# Heater_ADC.net
KiCad netlist of a schematic drawn in Altium Designer
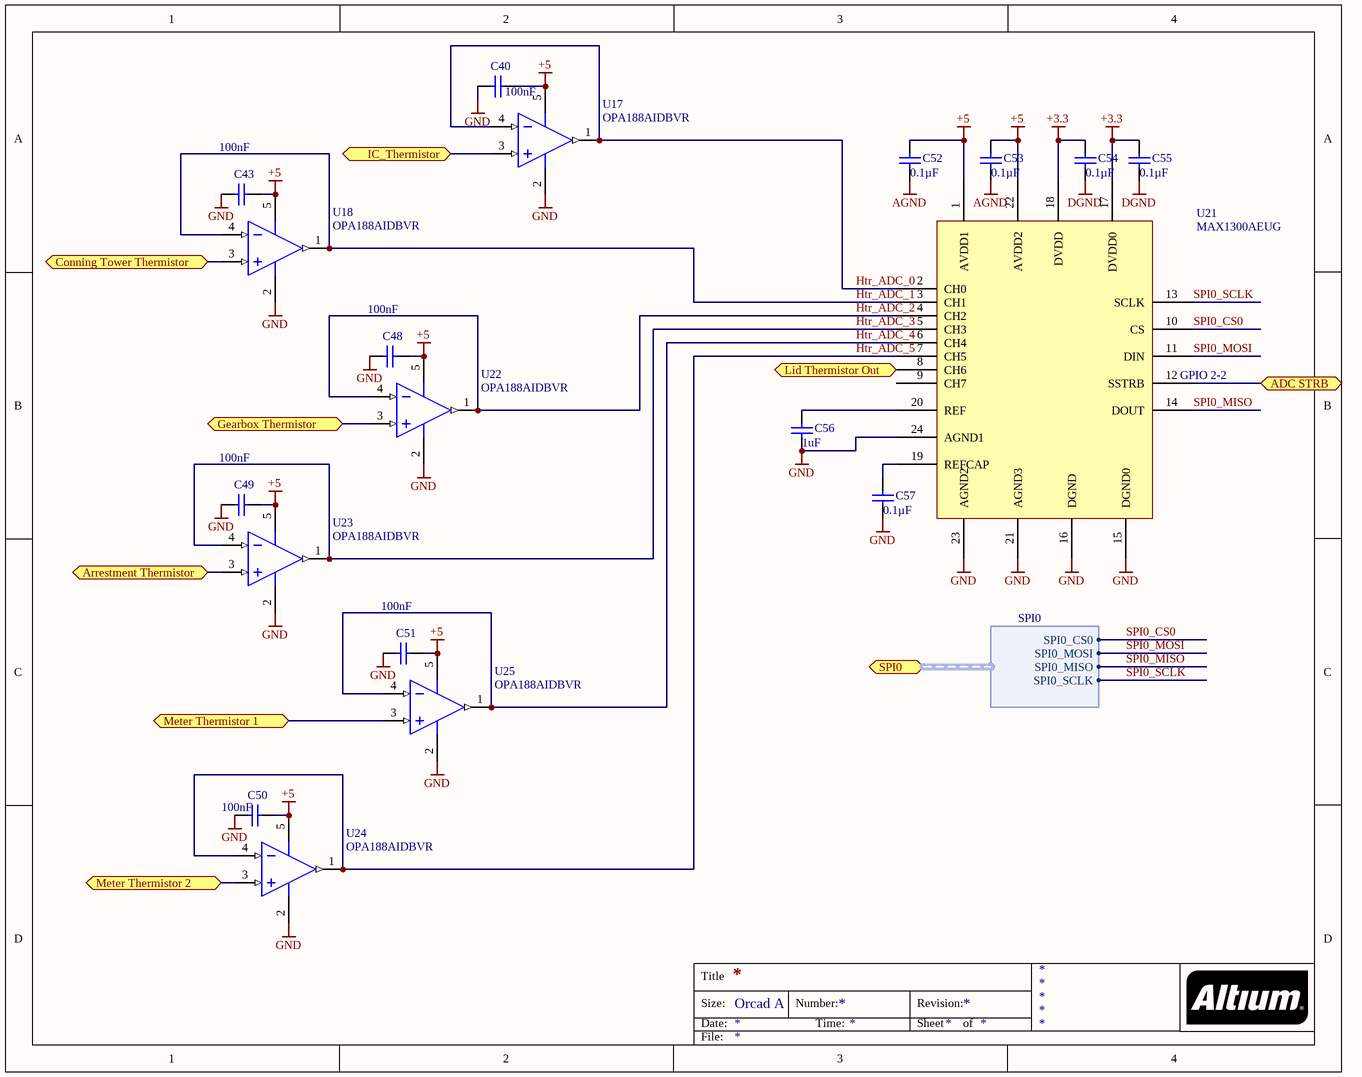
[diagram p0: Heater_ADC.SchDoc]

(export (version "E")
  (design (tool "Eeschema 10.0.6"))
  (components
    (comp (ref "C40")
      (value "~")
      (footprint "CAPC0402(1005)60_L")
      (fields
        (field (name "MANUFACTURER") "Kemet")
        (field (name "MANUFACTURER PART NUMBER") "C0402C104K4RACAUTO")
        (field (name "CAPACITANCE") "100nF")
        (field (name "TOLERANCE") "10%")
      )
      (libsource (lib "Altium Content Vault") (part "CMP-1034-01343-1"))
    )
    (comp (ref "C43")
      (value "~")
      (footprint "CAPC0402(1005)60_L")
      (fields
        (field (name "MANUFACTURER") "Kemet")
        (field (name "MANUFACTURER PART NUMBER") "C0402C104K4RACAUTO")
        (field (name "CAPACITANCE") "100nF")
        (field (name "TOLERANCE") "10%")
      )
      (libsource (lib "Altium Content Vault") (part "CMP-1034-01343-1"))
    )
    (comp (ref "C48")
      (value "~")
      (footprint "CAPC0402(1005)60_L")
      (fields
        (field (name "MANUFACTURER") "Kemet")
        (field (name "MANUFACTURER PART NUMBER") "C0402C104K4RACAUTO")
        (field (name "CAPACITANCE") "100nF")
        (field (name "TOLERANCE") "10%")
      )
      (libsource (lib "Altium Content Vault") (part "CMP-1034-01343-1"))
    )
    (comp (ref "C49")
      (value "~")
      (footprint "CAPC0402(1005)60_L")
      (fields
        (field (name "MANUFACTURER") "Kemet")
        (field (name "MANUFACTURER PART NUMBER") "C0402C104K4RACAUTO")
        (field (name "CAPACITANCE") "100nF")
        (field (name "TOLERANCE") "10%")
      )
      (libsource (lib "Altium Content Vault") (part "CMP-1034-01343-1"))
    )
    (comp (ref "C50")
      (value "~")
      (footprint "CAPC0402(1005)60_L")
      (fields
        (field (name "MANUFACTURER") "Kemet")
        (field (name "MANUFACTURER PART NUMBER") "C0402C104K4RACAUTO")
        (field (name "CAPACITANCE") "100nF")
        (field (name "TOLERANCE") "10%")
      )
      (libsource (lib "Altium Content Vault") (part "CMP-1034-01343-1"))
    )
    (comp (ref "C51")
      (value "~")
      (footprint "CAPC0402(1005)60_L")
      (fields
        (field (name "MANUFACTURER") "Kemet")
        (field (name "MANUFACTURER PART NUMBER") "C0402C104K4RACAUTO")
        (field (name "CAPACITANCE") "100nF")
        (field (name "TOLERANCE") "10%")
      )
      (libsource (lib "Altium Content Vault") (part "CMP-1034-01343-1"))
    )
    (comp (ref "C52")
      (value "CAP CER 0.1UF 25V X7R 0805")
      (footprint "CAPC0805(2012)145_N")
      (fields
        (field (name "MANUFACTURER") "Murata Electronics North America")
        (field (name "MANUFACTURER PART NUMBER") "GRM21BR71E104KA01L")
        (field (name "CAPACITANCE") "0.1µF")
        (field (name "TOLERANCE") "±10%")
      )
      (libsource (lib "Altium Content Vault") (part "CMP-1036-04795-1"))
    )
    (comp (ref "C53")
      (value "CAP CER 0.1UF 25V X7R 0805")
      (footprint "CAPC0805(2012)145_N")
      (fields
        (field (name "MANUFACTURER") "Murata Electronics North America")
        (field (name "MANUFACTURER PART NUMBER") "GRM21BR71E104KA01L")
        (field (name "CAPACITANCE") "0.1µF")
        (field (name "TOLERANCE") "±10%")
      )
      (libsource (lib "Altium Content Vault") (part "CMP-1036-04795-1"))
    )
    (comp (ref "C54")
      (value "CAP CER 0.1UF 25V X7R 0805")
      (footprint "CAPC0805(2012)145_N")
      (fields
        (field (name "MANUFACTURER") "Murata Electronics North America")
        (field (name "MANUFACTURER PART NUMBER") "GRM21BR71E104KA01L")
        (field (name "CAPACITANCE") "0.1µF")
        (field (name "TOLERANCE") "±10%")
      )
      (libsource (lib "Altium Content Vault") (part "CMP-1036-04795-1"))
    )
    (comp (ref "C55")
      (value "CAP CER 0.1UF 25V X7R 0805")
      (footprint "CAPC0805(2012)145_N")
      (fields
        (field (name "MANUFACTURER") "Murata Electronics North America")
        (field (name "MANUFACTURER PART NUMBER") "GRM21BR71E104KA01L")
        (field (name "CAPACITANCE") "0.1µF")
        (field (name "TOLERANCE") "±10%")
      )
      (libsource (lib "Altium Content Vault") (part "CMP-1036-04795-1"))
    )
    (comp (ref "C56")
      (value "CAP CER 1UF 16V X7R 0805")
      (footprint "CAPC0805(2012)145_N")
      (fields
        (field (name "MANUFACTURER") "Kemet")
        (field (name "MANUFACTURER PART NUMBER") "C0805X105K4RACTU")
        (field (name "CAPACITANCE") "1uF")
        (field (name "TOLERANCE") "10%")
      )
      (libsource (lib "Altium Content Vault") (part "CMP-1036-04795-1"))
    )
    (comp (ref "C57")
      (value "CAP CER 0.1UF 16V X7R 0805")
      (footprint "CAPC0805(2012)145_N")
      (fields
        (field (name "TOLERANCE") "±10%")
        (field (name "MANUFACTURER") "Murata Electronics North America")
        (field (name "MANUFACTURER PART NUMBER") "GRM219R71C104KA01D")
        (field (name "CAPACITANCE") "0.1µF")
      )
      (libsource (lib "Altium Content Vault") (part "CMP-1036-04795-1"))
    )
    (comp (ref "U17")
      (value "OPA188AIDBVR")
      (footprint "DBV0005A_M")
      (fields (field (name "MANUFACTURER") "Texas Instruments"))
      (libsource (lib "Altium Content Vault") (part "CMP-0809-00005-2"))
    )
    (comp (ref "U18")
      (value "OPA188AIDBVR")
      (footprint "DBV0005A_M")
      (fields (field (name "MANUFACTURER") "Texas Instruments"))
      (libsource (lib "Altium Content Vault") (part "CMP-0809-00005-2"))
    )
    (comp (ref "U21")
      (value "MAX1300AEUG")
      (footprint "TSOP65P640X90-24N")
      (description "IC ADC 16BIT SRL 115KSPS 24TSSOP")
      (libsource (lib "ZLS_LIB") (part "MAX1300AEUG"))
    )
    (comp (ref "U22")
      (value "OPA188AIDBVR")
      (footprint "DBV0005A_M")
      (fields (field (name "MANUFACTURER") "Texas Instruments"))
      (libsource (lib "Altium Content Vault") (part "CMP-0809-00005-2"))
    )
    (comp (ref "U23")
      (value "OPA188AIDBVR")
      (footprint "DBV0005A_M")
      (fields (field (name "MANUFACTURER") "Texas Instruments"))
      (libsource (lib "Altium Content Vault") (part "CMP-0809-00005-2"))
    )
    (comp (ref "U24")
      (value "OPA188AIDBVR")
      (footprint "DBV0005A_M")
      (fields (field (name "MANUFACTURER") "Texas Instruments"))
      (libsource (lib "Altium Content Vault") (part "CMP-0809-00005-2"))
    )
    (comp (ref "U25")
      (value "OPA188AIDBVR")
      (footprint "DBV0005A_M")
      (fields (field (name "MANUFACTURER") "Texas Instruments"))
      (libsource (lib "Altium Content Vault") (part "CMP-0809-00005-2"))
    )
  )
  (nets
    (net (code "2") (name "+3.3") (class "Default")
      (node (ref "C54") (pin "1") (pinfunction "1_1") (pintype "passive"))
      (node (ref "C55") (pin "1") (pinfunction "1_1") (pintype "passive"))
      (node (ref "U21") (pin "17") (pinfunction "DVDD0_17") (pintype "passive"))
      (node (ref "U21") (pin "18") (pinfunction "DVDD_18") (pintype "passive"))
    )
    (net (code "3") (name "+5") (class "Default")
      (node (ref "C40") (pin "2") (pinfunction "2_2") (pintype "passive"))
      (node (ref "C43") (pin "2") (pinfunction "2_2") (pintype "passive"))
      (node (ref "C48") (pin "2") (pinfunction "2_2") (pintype "passive"))
      (node (ref "C49") (pin "2") (pinfunction "2_2") (pintype "passive"))
      (node (ref "C50") (pin "2") (pinfunction "2_2") (pintype "passive"))
      (node (ref "C51") (pin "2") (pinfunction "2_2") (pintype "passive"))
      (node (ref "C52") (pin "1") (pinfunction "1_1") (pintype "passive"))
      (node (ref "C53") (pin "1") (pinfunction "1_1") (pintype "passive"))
      (node (ref "U17") (pin "5") (pinfunction "V+_5") (pintype "power_in"))
      (node (ref "U18") (pin "5") (pinfunction "V+_5") (pintype "power_in"))
      (node (ref "U21") (pin "1") (pinfunction "AVDD1_1") (pintype "passive"))
      (node (ref "U21") (pin "22") (pinfunction "AVDD2_22") (pintype "passive"))
      (node (ref "U22") (pin "5") (pinfunction "V+_5") (pintype "power_in"))
      (node (ref "U23") (pin "5") (pinfunction "V+_5") (pintype "power_in"))
      (node (ref "U24") (pin "5") (pinfunction "V+_5") (pintype "power_in"))
      (node (ref "U25") (pin "5") (pinfunction "V+_5") (pintype "power_in"))
    )
    (net (code "4") (name "/ADC STRB") (class "Default")
      (node (ref "U21") (pin "12") (pinfunction "SSTRB_12") (pintype "passive"))
    )
    (net (code "5") (name "/Arrestment Thermistor") (class "Default")
      (node (ref "U23") (pin "3") (pinfunction "IN+_3") (pintype "input"))
    )
    (net (code "6") (name "/Conning Tower Thermistor") (class "Default")
      (node (ref "U18") (pin "3") (pinfunction "IN+_3") (pintype "input"))
    )
    (net (code "7") (name "/Gearbox Thermistor") (class "Default")
      (node (ref "U22") (pin "3") (pinfunction "IN+_3") (pintype "input"))
    )
    (net (code "8") (name "/Htr_ADC_0") (class "Default")
      (node (ref "U17") (pin "1") (pinfunction "OUT_1") (pintype "output"))
      (node (ref "U17") (pin "4") (pinfunction "IN-_4") (pintype "input"))
      (node (ref "U21") (pin "2") (pinfunction "CH0_2") (pintype "passive"))
    )
    (net (code "9") (name "/Htr_ADC_1") (class "Default")
      (node (ref "U18") (pin "1") (pinfunction "OUT_1") (pintype "output"))
      (node (ref "U18") (pin "4") (pinfunction "IN-_4") (pintype "input"))
      (node (ref "U21") (pin "3") (pinfunction "CH1_3") (pintype "passive"))
    )
    (net (code "10") (name "/Htr_ADC_2") (class "Default")
      (node (ref "U21") (pin "4") (pinfunction "CH2_4") (pintype "passive"))
      (node (ref "U22") (pin "1") (pinfunction "OUT_1") (pintype "output"))
      (node (ref "U22") (pin "4") (pinfunction "IN-_4") (pintype "input"))
    )
    (net (code "11") (name "/Htr_ADC_3") (class "Default")
      (node (ref "U21") (pin "5") (pinfunction "CH3_5") (pintype "passive"))
      (node (ref "U23") (pin "1") (pinfunction "OUT_1") (pintype "output"))
      (node (ref "U23") (pin "4") (pinfunction "IN-_4") (pintype "input"))
    )
    (net (code "12") (name "/Htr_ADC_4") (class "Default")
      (node (ref "U21") (pin "6") (pinfunction "CH4_6") (pintype "passive"))
      (node (ref "U25") (pin "1") (pinfunction "OUT_1") (pintype "output"))
      (node (ref "U25") (pin "4") (pinfunction "IN-_4") (pintype "input"))
    )
    (net (code "13") (name "/Htr_ADC_5") (class "Default")
      (node (ref "U21") (pin "7") (pinfunction "CH5_7") (pintype "passive"))
      (node (ref "U24") (pin "1") (pinfunction "OUT_1") (pintype "output"))
      (node (ref "U24") (pin "4") (pinfunction "IN-_4") (pintype "input"))
    )
    (net (code "14") (name "/IC_Thermistor") (class "Default")
      (node (ref "U17") (pin "3") (pinfunction "IN+_3") (pintype "input"))
    )
    (net (code "15") (name "/Lid Thermistor Out") (class "Default")
      (node (ref "U21") (pin "8") (pinfunction "CH6_8") (pintype "passive"))
    )
    (net (code "16") (name "/Meter Thermistor 1") (class "Default")
      (node (ref "U25") (pin "3") (pinfunction "IN+_3") (pintype "input"))
    )
    (net (code "17") (name "/Meter Thermistor 2") (class "Default")
      (node (ref "U24") (pin "3") (pinfunction "IN+_3") (pintype "input"))
    )
    (net (code "18") (name "/SPI0_CS0") (class "Default")
      (node (ref "U21") (pin "10") (pinfunction "CS_10") (pintype "passive"))
    )
    (net (code "19") (name "/SPI0_MISO") (class "Default")
      (node (ref "U21") (pin "14") (pinfunction "DOUT_14") (pintype "passive"))
    )
    (net (code "20") (name "/SPI0_MOSI") (class "Default")
      (node (ref "U21") (pin "11") (pinfunction "DIN_11") (pintype "passive"))
    )
    (net (code "21") (name "/SPI0_SCLK") (class "Default")
      (node (ref "U21") (pin "13") (pinfunction "SCLK_13") (pintype "passive"))
    )
    (net (code "23") (name "AGND") (class "Default")
      (node (ref "C52") (pin "2") (pinfunction "2_2") (pintype "passive"))
      (node (ref "C53") (pin "2") (pinfunction "2_2") (pintype "passive"))
    )
    (net (code "24") (name "DGND") (class "Default")
      (node (ref "C54") (pin "2") (pinfunction "2_2") (pintype "passive"))
      (node (ref "C55") (pin "2") (pinfunction "2_2") (pintype "passive"))
    )
    (net (code "25") (name "GND") (class "Default")
      (node (ref "C40") (pin "1") (pinfunction "1_1") (pintype "passive"))
      (node (ref "C43") (pin "1") (pinfunction "1_1") (pintype "passive"))
      (node (ref "C48") (pin "1") (pinfunction "1_1") (pintype "passive"))
      (node (ref "C49") (pin "1") (pinfunction "1_1") (pintype "passive"))
      (node (ref "C50") (pin "1") (pinfunction "1_1") (pintype "passive"))
      (node (ref "C51") (pin "1") (pinfunction "1_1") (pintype "passive"))
      (node (ref "C56") (pin "2") (pinfunction "2_2") (pintype "passive"))
      (node (ref "C57") (pin "2") (pinfunction "2_2") (pintype "passive"))
      (node (ref "U17") (pin "2") (pinfunction "V-_2") (pintype "power_in"))
      (node (ref "U18") (pin "2") (pinfunction "V-_2") (pintype "power_in"))
      (node (ref "U21") (pin "15") (pinfunction "DGND0_15") (pintype "passive"))
      (node (ref "U21") (pin "16") (pinfunction "DGND_16") (pintype "passive"))
      (node (ref "U21") (pin "21") (pinfunction "AGND3_21") (pintype "passive"))
      (node (ref "U21") (pin "23") (pinfunction "AGND2_23") (pintype "passive"))
      (node (ref "U21") (pin "24") (pinfunction "AGND1_24") (pintype "passive"))
      (node (ref "U22") (pin "2") (pinfunction "V-_2") (pintype "power_in"))
      (node (ref "U23") (pin "2") (pinfunction "V-_2") (pintype "power_in"))
      (node (ref "U24") (pin "2") (pinfunction "V-_2") (pintype "power_in"))
      (node (ref "U25") (pin "2") (pinfunction "V-_2") (pintype "power_in"))
    )
    (net (code "26") (name "Net-(U21-REF)") (class "Default")
      (node (ref "C56") (pin "1") (pinfunction "1_1") (pintype "passive"))
      (node (ref "U21") (pin "20") (pinfunction "REF_20") (pintype "passive"))
    )
    (net (code "27") (name "Net-(U21-REFCAP)") (class "Default")
      (node (ref "C57") (pin "1") (pinfunction "1_1") (pintype "passive"))
      (node (ref "U21") (pin "19") (pinfunction "REFCAP_19") (pintype "passive"))
    )
    (net (code "28") (name "unconnected-(U21-CH7-Pad9)") (class "Default")
      (node (ref "U21") (pin "9") (pinfunction "CH7_9") (pintype "passive"))
    )
  )
)
